# N76E003_Kit.net
KiCad netlist of a schematic drawn in Altium Designer
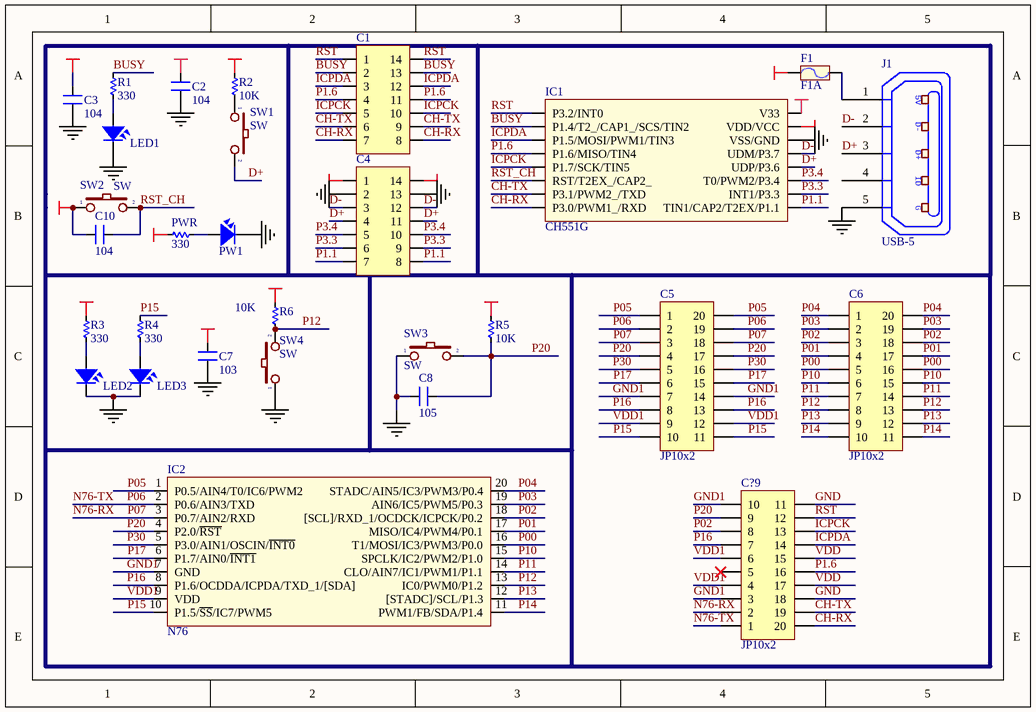
[diagram p0: [N76E003] Kit.SchDoc]

(export (version "E")
  (design (tool "Eeschema 10.0.6"))
  (components
    (comp (ref "C1")
      (value "JP7x2")
      (footprint "JP7-C2T")
      (description "WR-PHD 2.54 mm Dual Socket Header")
      (fields
        (field (name "MANUFACTURER") "Würth Elektronik eiSos GmbH")
        (field (name "PARTNO") "61301421821")
        (field (name "CREATED BY") "Karrer Zheng")
      )
      (libsource (lib "LIBRARY") (part "JP7x2"))
    )
    (comp (ref "C2")
      (value "104")
      (footprint "CN-SMD-0805")
      (description "Cap SMD")
      (libsource (lib "echipkool-com-library") (part "CM"))
    )
    (comp (ref "C3")
      (value "104")
      (footprint "CN-SMD-0805")
      (description "Cap SMD")
      (libsource (lib "echipkool-com-library") (part "CM"))
    )
    (comp (ref "C4")
      (value "JP7x2")
      (footprint "JP7-C2T")
      (description "WR-PHD 2.54 mm Dual Socket Header")
      (fields
        (field (name "MANUFACTURER") "Würth Elektronik eiSos GmbH")
        (field (name "PARTNO") "61301421821")
        (field (name "CREATED BY") "Karrer Zheng")
      )
      (libsource (lib "LIBRARY") (part "JP7x2"))
    )
    (comp (ref "C5")
      (value "JP10x2")
      (footprint "JP10-C2T")
      (description "WR-PHD 2.54 mm Dual Socket Header")
      (fields
        (field (name "MANUFACTURER") "Würth Elektronik eiSos GmbH")
        (field (name "PARTNO") "61302021821")
        (field (name "CREATED BY") "Karrer Zheng")
      )
      (libsource (lib "LIBRARY") (part "JP10x2"))
    )
    (comp (ref "C6")
      (value "JP10x2")
      (footprint "JP10-C2T")
      (description "WR-PHD 2.54 mm Dual Socket Header")
      (fields
        (field (name "MANUFACTURER") "Würth Elektronik eiSos GmbH")
        (field (name "PARTNO") "61302021821")
        (field (name "CREATED BY") "Karrer Zheng")
      )
      (libsource (lib "LIBRARY") (part "JP10x2"))
    )
    (comp (ref "C7")
      (value "103")
      (footprint "CN-SMD-0805")
      (description "Cap SMD")
      (libsource (lib "echipkool-com-library") (part "CM"))
    )
    (comp (ref "C8")
      (value "105")
      (footprint "CN-SMD-0805")
      (description "Cap SMD")
      (libsource (lib "echipkool-com-library") (part "CM"))
    )
    (comp (ref "C10")
      (value "104")
      (footprint "CN-SMD-0805")
      (description "Cap SMD")
      (libsource (lib "echipkool-com-library") (part "CM"))
    )
    (comp (ref "C?9")
      (value "JP10x2")
      (footprint "JP10-D2T")
      (description "WR-PHD 2.54 mm Dual Socket Header")
      (fields
        (field (name "MANUFACTURER") "Würth Elektronik eiSos GmbH")
        (field (name "PARTNO") "61302021821")
        (field (name "CREATED BY") "Karrer Zheng")
      )
      (libsource (lib "") (part "JP10x2_1"))
    )
    (comp (ref "F1")
      (value "F1A")
      (footprint "SM-RES-1206")
      (description "Fuse")
      (fields (field (name "DESIGNED BY") "VanDungEvn"))
      (libsource (lib "LIBRARY") (part "Fuse"))
    )
    (comp (ref "IC1") (value "CH551G") (footprint "Jmi:SOP16") (libsource (lib "Jmi") (part "[MCU] CH551G")))
    (comp (ref "IC2") (value "N76") (footprint "Jmi:TSSOP20") (libsource (lib "Jmi") (part "[MCU] N76E003")))
    (comp (ref "J1")
      (value "USB-5")
      (footprint "USB-M4")
      (fields
        (field (name "MANUFACTURER") "FCI")
        (field (name "MANUFACTURER PART NUMBER") "10118193-0001LF")
        (field (name ".CREATOR") "MM")
        (field (name ".CHECKED PCB") "RF")
        (field (name ".CHECKED SCH") "MM")
      )
      (libsource (lib "LIBRARY") (part "USB-5"))
    )
    (comp (ref "LED1")
      (value "LED")
      (footprint "LED-0805-Green")
      (libsource (lib "LIBRARY") (part "LED SMD"))
    )
    (comp (ref "LED2") (value "LED") (footprint "LED-0805-Red") (libsource (lib "LIBRARY") (part "LED SMD")))
    (comp (ref "LED3") (value "LED") (footprint "LED-0805-Blue") (libsource (lib "LIBRARY") (part "LED SMD")))
    (comp (ref "PW1") (value "LED") (footprint "LED-0805-Green") (libsource (lib "LIBRARY") (part "LED SMD")))
    (comp (ref "PWR")
      (value "330")
      (footprint "RES-SMD-0805")
      (description "Resistor")
      (fields
        (field (name "MANUFACTURER") "Generic Components")
        (field (name "PUBLISHER") "Altium Hobart Technology Centre")
      )
      (libsource (lib "LIBRARY") (part "Res-SMD"))
    )
    (comp (ref "R1")
      (value "330")
      (footprint "RES-SMD-0805")
      (description "Resistor")
      (fields
        (field (name "MANUFACTURER") "Generic Components")
        (field (name "PUBLISHER") "Altium Hobart Technology Centre")
      )
      (libsource (lib "LIBRARY") (part "Res-SMD"))
    )
    (comp (ref "R2")
      (value "10K")
      (footprint "RES-SMD-0805")
      (description "Resistor")
      (fields
        (field (name "MANUFACTURER") "Generic Components")
        (field (name "PUBLISHER") "Altium Hobart Technology Centre")
      )
      (libsource (lib "LIBRARY") (part "Res-SMD"))
    )
    (comp (ref "R3")
      (value "330")
      (footprint "RES-SMD-0805")
      (description "Resistor")
      (fields
        (field (name "MANUFACTURER") "Generic Components")
        (field (name "PUBLISHER") "Altium Hobart Technology Centre")
      )
      (libsource (lib "LIBRARY") (part "Res-SMD"))
    )
    (comp (ref "R4")
      (value "330")
      (footprint "RES-SMD-0805")
      (description "Resistor")
      (fields
        (field (name "MANUFACTURER") "Generic Components")
        (field (name "PUBLISHER") "Altium Hobart Technology Centre")
      )
      (libsource (lib "LIBRARY") (part "Res-SMD"))
    )
    (comp (ref "R5")
      (value "10K")
      (footprint "RES-SMD-0805")
      (description "Resistor")
      (fields
        (field (name "MANUFACTURER") "Generic Components")
        (field (name "PUBLISHER") "Altium Hobart Technology Centre")
      )
      (libsource (lib "LIBRARY") (part "Res-SMD"))
    )
    (comp (ref "R6")
      (value "10K")
      (footprint "RES-SMD-0805")
      (description "Resistor")
      (fields
        (field (name "MANUFACTURER") "Generic Components")
        (field (name "PUBLISHER") "Altium Hobart Technology Centre")
      )
      (libsource (lib "LIBRARY") (part "Res-SMD"))
    )
    (comp (ref "SW1")
      (value "SW")
      (footprint "SW1-SMD")
      (description "Switch button 2 pin")
      (libsource (lib "LIBRARY") (part "SW2"))
    )
    (comp (ref "SW2")
      (value "SW")
      (footprint "SW1-SMD")
      (description "Switch button 2 pin")
      (libsource (lib "LIBRARY") (part "SW2"))
    )
    (comp (ref "SW3")
      (value "SW")
      (footprint "SW1-SMD")
      (description "Switch button 2 pin")
      (libsource (lib "LIBRARY") (part "SW2"))
    )
    (comp (ref "SW4")
      (value "SW")
      (footprint "SW1-SMD")
      (description "Switch button 2 pin")
      (libsource (lib "LIBRARY") (part "SW2"))
    )
  )
  (nets
    (net (code "1") (name "+3.3v") (class "Default")
      (node (ref "C2") (pin "2") (pinfunction "2_2") (pintype "passive"))
      (node (ref "IC1") (pin "16") (pinfunction "V33_16") (pintype "power_in"))
    )
    (net (code "2") (name "/BUSY") (class "Default")
      (node (ref "C1") (pin "13") (pinfunction "13_13") (pintype "passive"))
      (node (ref "C1") (pin "2") (pinfunction "2_2") (pintype "passive"))
      (node (ref "IC1") (pin "2") (pinfunction "P1.4/T2_/CAP1_/SCS/TIN2_2") (pintype "power_in"))
      (node (ref "R1") (pin "1") (pinfunction "1_1") (pintype "passive"))
    )
    (net (code "3") (name "/CH-RX") (class "Default")
      (node (ref "C1") (pin "7") (pinfunction "7_7") (pintype "passive"))
      (node (ref "C1") (pin "8") (pinfunction "8_8") (pintype "passive"))
      (node (ref "C?9") (pin "20") (pinfunction "20_20") (pintype "passive"))
      (node (ref "IC1") (pin "8") (pinfunction "P3.0/PWM1_/RXD_8") (pintype "power_in"))
    )
    (net (code "4") (name "/CH-TX") (class "Default")
      (node (ref "C1") (pin "6") (pinfunction "6_6") (pintype "passive"))
      (node (ref "C1") (pin "9") (pinfunction "9_9") (pintype "passive"))
      (node (ref "C?9") (pin "19") (pinfunction "19_19") (pintype "passive"))
      (node (ref "IC1") (pin "7") (pinfunction "P3.1/PWM2_/TXD_7") (pintype "power_in"))
    )
    (net (code "5") (name "/D+") (class "Default")
      (node (ref "C4") (pin "11") (pinfunction "11_11") (pintype "passive"))
      (node (ref "C4") (pin "4") (pinfunction "4_4") (pintype "passive"))
      (node (ref "IC1") (pin "12") (pinfunction "UDP/P3.6_12") (pintype "power_in"))
      (node (ref "J1") (pin "3") (pinfunction "P3_3") (pintype "passive"))
      (node (ref "SW1") (pin "2") (pinfunction "2_2") (pintype "passive"))
    )
    (net (code "6") (name "/D-") (class "Default")
      (node (ref "C4") (pin "12") (pinfunction "12_12") (pintype "passive"))
      (node (ref "C4") (pin "3") (pinfunction "3_3") (pintype "passive"))
      (node (ref "IC1") (pin "13") (pinfunction "UDM/P3.7_13") (pintype "power_in"))
      (node (ref "J1") (pin "2") (pinfunction "P2_2") (pintype "passive"))
    )
    (net (code "7") (name "/ICPCK") (class "Default")
      (node (ref "C1") (pin "10") (pinfunction "10_10") (pintype "passive"))
      (node (ref "C1") (pin "5") (pinfunction "5_5") (pintype "passive"))
      (node (ref "C?9") (pin "13") (pinfunction "13_13") (pintype "passive"))
      (node (ref "IC1") (pin "5") (pinfunction "P1.7/SCK/TIN5_5") (pintype "power_in"))
    )
    (net (code "8") (name "/ICPDA") (class "Default")
      (node (ref "C1") (pin "12") (pinfunction "12_12") (pintype "passive"))
      (node (ref "C1") (pin "3") (pinfunction "3_3") (pintype "passive"))
      (node (ref "C?9") (pin "14") (pinfunction "14_14") (pintype "passive"))
      (node (ref "IC1") (pin "3") (pinfunction "P1.5/MOSI/PWM1/TIN3_3") (pintype "power_in"))
    )
    (net (code "9") (name "/N76-RX") (class "Default")
      (node (ref "C5") (pin "18") (pinfunction "18_18") (pintype "passive"))
      (node (ref "C5") (pin "3") (pinfunction "3_3") (pintype "passive"))
      (node (ref "C?9") (pin "2") (pinfunction "2_2") (pintype "passive"))
      (node (ref "IC2") (pin "3") (pinfunction "P0.7/AIN2/RXD_3") (pintype "passive"))
    )
    (net (code "10") (name "/N76-TX") (class "Default")
      (node (ref "C5") (pin "19") (pinfunction "19_19") (pintype "passive"))
      (node (ref "C5") (pin "2") (pinfunction "2_2") (pintype "passive"))
      (node (ref "C?9") (pin "1") (pinfunction "1_1") (pintype "passive"))
      (node (ref "IC2") (pin "2") (pinfunction "P0.6/AIN3/TXD_2") (pintype "passive"))
    )
    (net (code "11") (name "/P00") (class "Default")
      (node (ref "C6") (pin "16") (pinfunction "16_16") (pintype "passive"))
      (node (ref "C6") (pin "5") (pinfunction "5_5") (pintype "passive"))
      (node (ref "IC2") (pin "16") (pinfunction "T1/MOSI/IC3/PWM3/P0.0_16") (pintype "passive"))
    )
    (net (code "12") (name "/P01") (class "Default")
      (node (ref "C6") (pin "17") (pinfunction "17_17") (pintype "passive"))
      (node (ref "C6") (pin "4") (pinfunction "4_4") (pintype "passive"))
      (node (ref "IC2") (pin "17") (pinfunction "MISO/IC4/PWM4/P0.1_17") (pintype "passive"))
    )
    (net (code "13") (name "/P1.1") (class "Default")
      (node (ref "C4") (pin "7") (pinfunction "7_7") (pintype "passive"))
      (node (ref "C4") (pin "8") (pinfunction "8_8") (pintype "passive"))
      (node (ref "IC1") (pin "9") (pinfunction "TIN1/CAP2/T2EX/P1.1_9") (pintype "power_in"))
    )
    (net (code "14") (name "/P1.6") (class "Default")
      (node (ref "C1") (pin "11") (pinfunction "11_11") (pintype "passive"))
      (node (ref "C1") (pin "4") (pinfunction "4_4") (pintype "passive"))
      (node (ref "C?9") (pin "16") (pinfunction "16_16") (pintype "passive"))
      (node (ref "IC1") (pin "4") (pinfunction "P1.6/MISO/TIN4_4") (pintype "power_in"))
    )
    (net (code "15") (name "/P02") (class "Default")
      (node (ref "C6") (pin "18") (pinfunction "18_18") (pintype "passive"))
      (node (ref "C6") (pin "3") (pinfunction "3_3") (pintype "passive"))
      (node (ref "C?9") (pin "8") (pinfunction "8_8") (pintype "passive"))
      (node (ref "IC2") (pin "18") (pinfunction "[SCL]/RXD_1/OCDCK/ICPCK/P0.2_18") (pintype "passive"))
    )
    (net (code "16") (name "/P03") (class "Default")
      (node (ref "C6") (pin "19") (pinfunction "19_19") (pintype "passive"))
      (node (ref "C6") (pin "2") (pinfunction "2_2") (pintype "passive"))
      (node (ref "IC2") (pin "19") (pinfunction "AIN6/IC5/PWM5/P0.3_19") (pintype "passive"))
    )
    (net (code "17") (name "/P3.3") (class "Default")
      (node (ref "C4") (pin "6") (pinfunction "6_6") (pintype "passive"))
      (node (ref "C4") (pin "9") (pinfunction "9_9") (pintype "passive"))
      (node (ref "IC1") (pin "10") (pinfunction "INT1/P3.3_10") (pintype "power_in"))
    )
    (net (code "18") (name "/P3.4") (class "Default")
      (node (ref "C4") (pin "10") (pinfunction "10_10") (pintype "passive"))
      (node (ref "C4") (pin "5") (pinfunction "5_5") (pintype "passive"))
      (node (ref "IC1") (pin "11") (pinfunction "T0/PWM2/P3.4_11") (pintype "power_in"))
    )
    (net (code "19") (name "/P04") (class "Default")
      (node (ref "C6") (pin "1") (pinfunction "1_1") (pintype "passive"))
      (node (ref "C6") (pin "20") (pinfunction "20_20") (pintype "passive"))
      (node (ref "IC2") (pin "20") (pinfunction "STADC/AIN5/IC3/PWM3/P0.4_20") (pintype "passive"))
    )
    (net (code "20") (name "/P05") (class "Default")
      (node (ref "C5") (pin "1") (pinfunction "1_1") (pintype "passive"))
      (node (ref "C5") (pin "20") (pinfunction "20_20") (pintype "passive"))
      (node (ref "IC2") (pin "1") (pinfunction "P0.5/AIN4/T0/IC6/PWM2_1") (pintype "passive"))
    )
    (net (code "21") (name "/P10") (class "Default")
      (node (ref "C6") (pin "15") (pinfunction "15_15") (pintype "passive"))
      (node (ref "C6") (pin "6") (pinfunction "6_6") (pintype "passive"))
      (node (ref "IC2") (pin "15") (pinfunction "SPCLK/IC2/PWM2/P1.0_15") (pintype "passive"))
    )
    (net (code "22") (name "/P11") (class "Default")
      (node (ref "C6") (pin "14") (pinfunction "14_14") (pintype "passive"))
      (node (ref "C6") (pin "7") (pinfunction "7_7") (pintype "passive"))
      (node (ref "IC2") (pin "14") (pinfunction "CLO/AIN7/IC1/PWM1/P1.1_14") (pintype "passive"))
    )
    (net (code "23") (name "/P12") (class "Default")
      (node (ref "C6") (pin "13") (pinfunction "13_13") (pintype "passive"))
      (node (ref "C6") (pin "8") (pinfunction "8_8") (pintype "passive"))
      (node (ref "IC2") (pin "13") (pinfunction "IC0/PWM0/P1.2_13") (pintype "passive"))
      (node (ref "R6") (pin "2") (pinfunction "2_2") (pintype "passive"))
      (node (ref "SW4") (pin "2") (pinfunction "2_2") (pintype "passive"))
    )
    (net (code "24") (name "/P13") (class "Default")
      (node (ref "C6") (pin "12") (pinfunction "12_12") (pintype "passive"))
      (node (ref "C6") (pin "9") (pinfunction "9_9") (pintype "passive"))
      (node (ref "IC2") (pin "12") (pinfunction "[STADC]/SCL/P1.3_12") (pintype "passive"))
    )
    (net (code "25") (name "/P14") (class "Default")
      (node (ref "C6") (pin "10") (pinfunction "10_10") (pintype "passive"))
      (node (ref "C6") (pin "11") (pinfunction "11_11") (pintype "passive"))
      (node (ref "IC2") (pin "11") (pinfunction "PWM1/FB/SDA/P1.4_11") (pintype "passive"))
    )
    (net (code "26") (name "/P15") (class "Default")
      (node (ref "C5") (pin "10") (pinfunction "10_10") (pintype "passive"))
      (node (ref "C5") (pin "11") (pinfunction "11_11") (pintype "passive"))
      (node (ref "IC2") (pin "10") (pinfunction "P1.5/~{SS}/IC7/PWM5_10") (pintype "passive"))
      (node (ref "R4") (pin "1") (pinfunction "1_1") (pintype "passive"))
    )
    (net (code "27") (name "/P16") (class "Default")
      (node (ref "C5") (pin "13") (pinfunction "13_13") (pintype "passive"))
      (node (ref "C5") (pin "8") (pinfunction "8_8") (pintype "passive"))
      (node (ref "C?9") (pin "7") (pinfunction "7_7") (pintype "passive"))
      (node (ref "IC2") (pin "8") (pinfunction "P1.6/OCDDA/ICPDA/TXD_1/[SDA]_8") (pintype "passive"))
    )
    (net (code "28") (name "/P17") (class "Default")
      (node (ref "C5") (pin "15") (pinfunction "15_15") (pintype "passive"))
      (node (ref "C5") (pin "6") (pinfunction "6_6") (pintype "passive"))
      (node (ref "IC2") (pin "6") (pinfunction "P1.7/AIN0/~{INT1}_6") (pintype "passive"))
    )
    (net (code "29") (name "/P20") (class "Default")
      (node (ref "C5") (pin "17") (pinfunction "17_17") (pintype "passive"))
      (node (ref "C5") (pin "4") (pinfunction "4_4") (pintype "passive"))
      (node (ref "C8") (pin "1") (pinfunction "1_1") (pintype "passive"))
      (node (ref "C?9") (pin "9") (pinfunction "9_9") (pintype "passive"))
      (node (ref "IC2") (pin "4") (pinfunction "P2.0/~{RST}_4") (pintype "passive"))
      (node (ref "R5") (pin "2") (pinfunction "2_2") (pintype "passive"))
      (node (ref "SW3") (pin "2") (pinfunction "2_2") (pintype "passive"))
    )
    (net (code "30") (name "/P30") (class "Default")
      (node (ref "C5") (pin "16") (pinfunction "16_16") (pintype "passive"))
      (node (ref "C5") (pin "5") (pinfunction "5_5") (pintype "passive"))
      (node (ref "IC2") (pin "5") (pinfunction "P3.0/AIN1/OSCIN/~{INT0}_5") (pintype "passive"))
    )
    (net (code "31") (name "/RST") (class "Default")
      (node (ref "C1") (pin "1") (pinfunction "1_1") (pintype "passive"))
      (node (ref "C1") (pin "14") (pinfunction "14_14") (pintype "passive"))
      (node (ref "C?9") (pin "12") (pinfunction "12_12") (pintype "passive"))
      (node (ref "IC1") (pin "1") (pinfunction "P3.2/INT0_1") (pintype "power_in"))
    )
    (net (code "32") (name "/RST_CH") (class "Default")
      (node (ref "C10") (pin "1") (pinfunction "1_1") (pintype "passive"))
      (node (ref "IC1") (pin "6") (pinfunction "RST/T2EX_/CAP2__6") (pintype "power_in"))
      (node (ref "SW2") (pin "2") (pinfunction "2_2") (pintype "passive"))
    )
    (net (code "33") (name "GND") (class "Default")
      (node (ref "C2") (pin "1") (pinfunction "1_1") (pintype "passive"))
      (node (ref "C3") (pin "1") (pinfunction "1_1") (pintype "passive"))
      (node (ref "C4") (pin "13") (pinfunction "13_13") (pintype "passive"))
      (node (ref "C4") (pin "2") (pinfunction "2_2") (pintype "passive"))
      (node (ref "C?9") (pin "11") (pinfunction "11_11") (pintype "passive"))
      (node (ref "C?9") (pin "18") (pinfunction "18_18") (pintype "passive"))
      (node (ref "IC1") (pin "14") (pinfunction "VSS/GND_14") (pintype "power_in"))
      (node (ref "J1") (pin "5") (pinfunction "P5_5") (pintype "passive"))
      (node (ref "LED1") (pin "2") (pinfunction "2_2") (pintype "passive"))
      (node (ref "PW1") (pin "2") (pinfunction "2_2") (pintype "passive"))
    )
    (net (code "34") (name "GND1") (class "Default")
      (node (ref "C5") (pin "14") (pinfunction "14_14") (pintype "passive"))
      (node (ref "C5") (pin "7") (pinfunction "7_7") (pintype "passive"))
      (node (ref "C7") (pin "1") (pinfunction "1_1") (pintype "passive"))
      (node (ref "C8") (pin "2") (pinfunction "2_2") (pintype "passive"))
      (node (ref "C?9") (pin "10") (pinfunction "10_10") (pintype "passive"))
      (node (ref "C?9") (pin "3") (pinfunction "3_3") (pintype "passive"))
      (node (ref "IC2") (pin "7") (pinfunction "GND_7") (pintype "power_in"))
      (node (ref "LED2") (pin "2") (pinfunction "2_2") (pintype "passive"))
      (node (ref "LED3") (pin "2") (pinfunction "2_2") (pintype "passive"))
      (node (ref "SW3") (pin "1") (pinfunction "1_1") (pintype "passive"))
      (node (ref "SW4") (pin "1") (pinfunction "1_1") (pintype "passive"))
    )
    (net (code "35") (name "Net-(J1-P1)") (class "Default")
      (node (ref "F1") (pin "1") (pinfunction "1_1") (pintype "passive"))
      (node (ref "J1") (pin "1") (pinfunction "P1_1") (pintype "passive"))
    )
    (net (code "36") (name "Net-(LED1-Pad1)") (class "Default")
      (node (ref "LED1") (pin "1") (pinfunction "1_1") (pintype "passive"))
      (node (ref "R1") (pin "2") (pinfunction "2_2") (pintype "passive"))
    )
    (net (code "37") (name "Net-(LED2-Pad1)") (class "Default")
      (node (ref "LED2") (pin "1") (pinfunction "1_1") (pintype "passive"))
      (node (ref "R3") (pin "2") (pinfunction "2_2") (pintype "passive"))
    )
    (net (code "38") (name "Net-(LED3-Pad1)") (class "Default")
      (node (ref "LED3") (pin "1") (pinfunction "1_1") (pintype "passive"))
      (node (ref "R4") (pin "2") (pinfunction "2_2") (pintype "passive"))
    )
    (net (code "39") (name "Net-(PW1-Pad1)") (class "Default")
      (node (ref "PW1") (pin "1") (pinfunction "1_1") (pintype "passive"))
      (node (ref "PWR") (pin "2") (pinfunction "2_2") (pintype "passive"))
    )
    (net (code "40") (name "Net-(R2-Pad2)") (class "Default")
      (node (ref "R2") (pin "2") (pinfunction "2_2") (pintype "passive"))
      (node (ref "SW1") (pin "1") (pinfunction "1_1") (pintype "passive"))
    )
    (net (code "41") (name "VDD") (class "Default")
      (node (ref "C10") (pin "2") (pinfunction "2_2") (pintype "passive"))
      (node (ref "C3") (pin "2") (pinfunction "2_2") (pintype "passive"))
      (node (ref "C4") (pin "1") (pinfunction "1_1") (pintype "passive"))
      (node (ref "C4") (pin "14") (pinfunction "14_14") (pintype "passive"))
      (node (ref "C?9") (pin "15") (pinfunction "15_15") (pintype "passive"))
      (node (ref "C?9") (pin "17") (pinfunction "17_17") (pintype "passive"))
      (node (ref "F1") (pin "2") (pinfunction "2_2") (pintype "passive"))
      (node (ref "IC1") (pin "15") (pinfunction "VDD/VCC_15") (pintype "power_in"))
      (node (ref "PWR") (pin "1") (pinfunction "1_1") (pintype "passive"))
      (node (ref "R2") (pin "1") (pinfunction "1_1") (pintype "passive"))
      (node (ref "SW2") (pin "1") (pinfunction "1_1") (pintype "passive"))
    )
    (net (code "42") (name "VDD1") (class "Default")
      (node (ref "C5") (pin "12") (pinfunction "12_12") (pintype "passive"))
      (node (ref "C5") (pin "9") (pinfunction "9_9") (pintype "passive"))
      (node (ref "C7") (pin "2") (pinfunction "2_2") (pintype "passive"))
      (node (ref "C?9") (pin "4") (pinfunction "4_4") (pintype "passive"))
      (node (ref "C?9") (pin "6") (pinfunction "6_6") (pintype "passive"))
      (node (ref "IC2") (pin "9") (pinfunction "VDD_9") (pintype "power_in"))
      (node (ref "R3") (pin "1") (pinfunction "1_1") (pintype "passive"))
      (node (ref "R5") (pin "1") (pinfunction "1_1") (pintype "passive"))
      (node (ref "R6") (pin "1") (pinfunction "1_1") (pintype "passive"))
    )
    (net (code "43") (name "unconnected-(C?9-Pad5)") (class "Default")
      (node (ref "C?9") (pin "5") (pinfunction "5_5") (pintype "passive+no_connect"))
    )
    (net (code "44") (name "unconnected-(J1-P4-Pad4)") (class "Default")
      (node (ref "J1") (pin "4") (pinfunction "P4_4") (pintype "passive"))
    )
  )
)
